# VolcanoHat.net
KiCad netlist of a schematic drawn in EAGLE
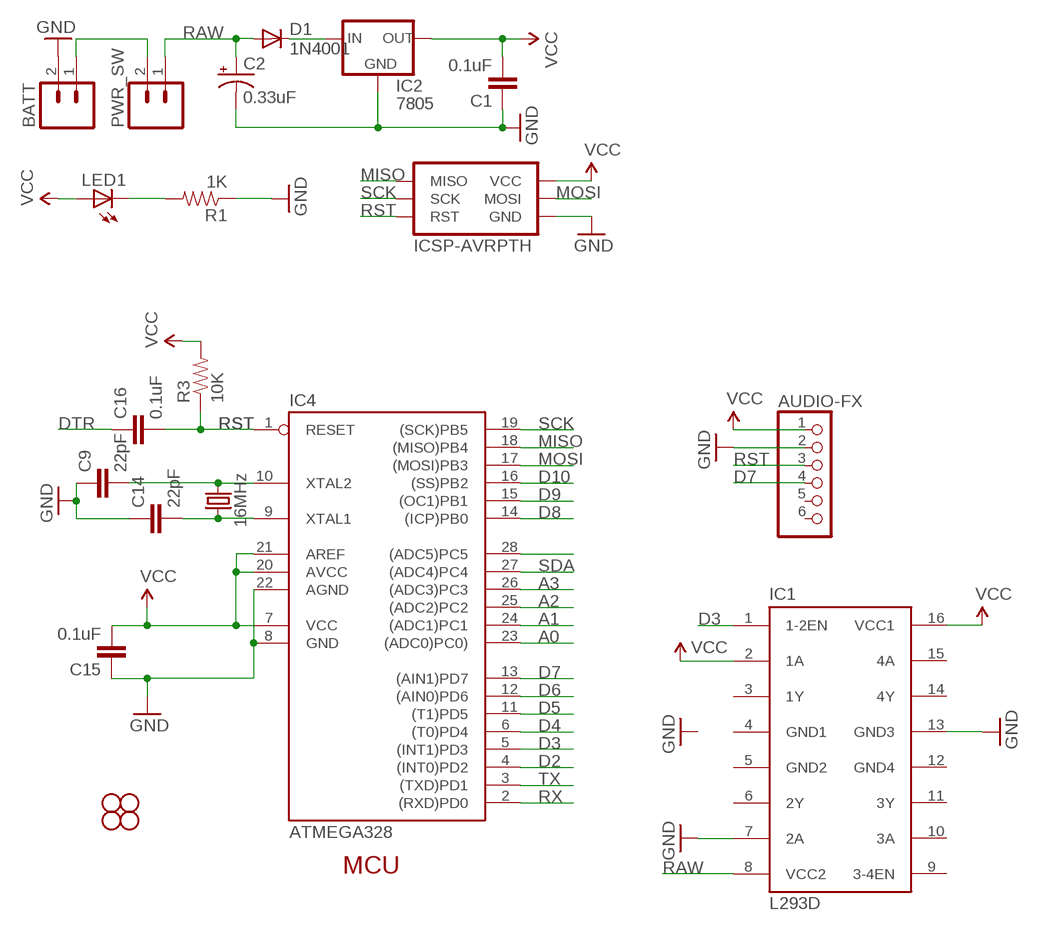
[diagram p0: schematic, sheet 1]

(export (version "E")
  (design (tool "Eeschema 10.0.6"))
  (components
    (comp (ref "AUDIO-FX")
      (value "PINHD-1X6")
      (footprint "eagle-import:1X06")
      (libsource (lib "eagle-import") (part "PINHD-1X6"))
    )
    (comp (ref "BATT")
      (value "M02LOCK_LONGPADS")
      (footprint "eagle-import:1X02_LOCK_LONGPADS")
      (libsource (lib "eagle-import") (part "M02LOCK_LONGPADS"))
    )
    (comp (ref "C1")
      (value "0.1uF")
      (footprint "eagle-import:CAP-PTH-SMALL2")
      (libsource (lib "eagle-import") (part "CAPPTH2"))
    )
    (comp (ref "C2")
      (value "0.33uF")
      (footprint "eagle-import:CPOL-RADIAL-10UF-25V")
      (libsource (lib "eagle-import") (part "CAP_POLPTH2"))
    )
    (comp (ref "C9")
      (value "22pF")
      (footprint "eagle-import:CAP-PTH-SMALL2")
      (libsource (lib "eagle-import") (part "CAPPTH2"))
    )
    (comp (ref "C14")
      (value "22pF")
      (footprint "eagle-import:CAP-PTH-SMALL2")
      (libsource (lib "eagle-import") (part "CAPPTH2"))
    )
    (comp (ref "C15")
      (value "0.1uF")
      (footprint "eagle-import:CAP-PTH-SMALL2")
      (libsource (lib "eagle-import") (part "CAPPTH2"))
    )
    (comp (ref "C16")
      (value "0.1uF")
      (footprint "eagle-import:CAP-PTH-SMALL2")
      (libsource (lib "eagle-import") (part "CAPPTH2"))
    )
    (comp (ref "D1")
      (value "1N4001")
      (footprint "eagle-import:DIODE-1N4001")
      (libsource (lib "eagle-import") (part "DIODEPTH"))
    )
    (comp (ref "IC1")
      (value "L293D")
      (footprint "eagle-import:DIL16")
      (libsource (lib "eagle-import") (part "L293D"))
    )
    (comp (ref "IC2")
      (value "7805")
      (footprint "eagle-import:TO220-IGO")
      (libsource (lib "eagle-import") (part "V_REG_78XXSINK"))
    )
    (comp (ref "IC4")
      (value "ATMEGA328")
      (footprint "eagle-import:DIL28-3")
      (libsource (lib "eagle-import") (part "AT90S4433P"))
    )
    (comp (ref "ICSP")
      (value "ICSP-AVRPTH")
      (footprint "eagle-import:2X3-SHROUDED")
      (libsource (lib "eagle-import") (part "ICSP-AVRPTH"))
    )
    (comp (ref "JP1")
      (value "STAND-OFF#2")
      (footprint "eagle-import:STAND-OFF-#2")
      (libsource (lib "eagle-import") (part "STAND-OFF#2"))
    )
    (comp (ref "JP2")
      (value "STAND-OFF#2")
      (footprint "eagle-import:STAND-OFF-#2")
      (libsource (lib "eagle-import") (part "STAND-OFF#2"))
    )
    (comp (ref "JP5")
      (value "STAND-OFF#2")
      (footprint "eagle-import:STAND-OFF-#2")
      (libsource (lib "eagle-import") (part "STAND-OFF#2"))
    )
    (comp (ref "JP6")
      (value "STAND-OFF#2")
      (footprint "eagle-import:STAND-OFF-#2")
      (libsource (lib "eagle-import") (part "STAND-OFF#2"))
    )
    (comp (ref "LED1")
      (value "LED5MM")
      (footprint "eagle-import:LED5MM")
      (libsource (lib "eagle-import") (part "LED5MM"))
    )
    (comp (ref "PWR_SW")
      (value "M02LOCK_LONGPADS")
      (footprint "eagle-import:1X02_LOCK_LONGPADS")
      (libsource (lib "eagle-import") (part "M02LOCK_LONGPADS"))
    )
    (comp (ref "R1")
      (value "1K")
      (footprint "eagle-import:AXIAL-0.3")
      (libsource (lib "eagle-import") (part "RESISTORAXIAL-0.3"))
    )
    (comp (ref "R3")
      (value "10K")
      (footprint "eagle-import:AXIAL-0.3")
      (libsource (lib "eagle-import") (part "RESISTORAXIAL-0.3"))
    )
    (comp (ref "Y1")
      (value "16MHz")
      (footprint "eagle-import:HC49US")
      (libsource (lib "eagle-import") (part "CRYSTALHC49US"))
    )
  )
  (nets
    (net (code "1") (name "/A0") (class "Default")
      (node (ref "IC4") (pin "23") (pinfunction "(ADC0)PC0)_23") (pintype "bidirectional"))
    )
    (net (code "2") (name "/A1") (class "Default")
      (node (ref "IC4") (pin "24") (pinfunction "(ADC1)PC1_24") (pintype "bidirectional"))
    )
    (net (code "3") (name "/A2") (class "Default")
      (node (ref "IC4") (pin "25") (pinfunction "(ADC2)PC2_25") (pintype "bidirectional"))
    )
    (net (code "4") (name "/A3") (class "Default")
      (node (ref "IC4") (pin "26") (pinfunction "(ADC3)PC3_26") (pintype "bidirectional"))
    )
    (net (code "5") (name "/D2") (class "Default")
      (node (ref "IC4") (pin "4") (pinfunction "(INT0)PD2_4") (pintype "bidirectional"))
    )
    (net (code "6") (name "/D3") (class "Default")
      (node (ref "IC1") (pin "1") (pinfunction "1-2EN_1") (pintype "input"))
      (node (ref "IC4") (pin "5") (pinfunction "(INT1)PD3_5") (pintype "bidirectional"))
    )
    (net (code "7") (name "/D4") (class "Default")
      (node (ref "IC4") (pin "6") (pinfunction "(T0)PD4_6") (pintype "bidirectional"))
    )
    (net (code "8") (name "/D5") (class "Default")
      (node (ref "IC4") (pin "11") (pinfunction "(T1)PD5_11") (pintype "bidirectional"))
    )
    (net (code "9") (name "/D6") (class "Default")
      (node (ref "IC4") (pin "12") (pinfunction "(AIN0)PD6_12") (pintype "bidirectional"))
    )
    (net (code "10") (name "/D7") (class "Default")
      (node (ref "AUDIO-FX") (pin "4") (pinfunction "4_4") (pintype "passive"))
      (node (ref "IC4") (pin "13") (pinfunction "(AIN1)PD7_13") (pintype "bidirectional"))
    )
    (net (code "11") (name "/D8") (class "Default")
      (node (ref "IC4") (pin "14") (pinfunction "(ICP)PB0_14") (pintype "bidirectional"))
    )
    (net (code "12") (name "/D9") (class "Default")
      (node (ref "IC4") (pin "15") (pinfunction "(OC1)PB1_15") (pintype "bidirectional"))
    )
    (net (code "13") (name "/D10") (class "Default")
      (node (ref "IC4") (pin "16") (pinfunction "(SS)PB2_16") (pintype "bidirectional"))
    )
    (net (code "14") (name "/DTR") (class "Default")
      (node (ref "C16") (pin "1") (pinfunction "1_1") (pintype "passive"))
    )
    (net (code "15") (name "/GND1") (class "Default")
      (node (ref "IC1") (pin "4") (pinfunction "GND1_4") (pintype "power_in"))
    )
    (net (code "16") (name "/GND2") (class "Default")
      (node (ref "IC1") (pin "5") (pinfunction "GND2_5") (pintype "power_in"))
    )
    (net (code "17") (name "/GND4") (class "Default")
      (node (ref "IC1") (pin "12") (pinfunction "GND4_12") (pintype "power_in"))
    )
    (net (code "18") (name "/MISO") (class "Default")
      (node (ref "IC4") (pin "18") (pinfunction "(MISO)PB4_18") (pintype "bidirectional"))
      (node (ref "ICSP") (pin "1") (pinfunction "MISO_1") (pintype "bidirectional"))
    )
    (net (code "19") (name "/MOSI") (class "Default")
      (node (ref "IC4") (pin "17") (pinfunction "(MOSI)PB3_17") (pintype "bidirectional"))
      (node (ref "ICSP") (pin "4") (pinfunction "MOSI_4") (pintype "bidirectional"))
    )
    (net (code "20") (name "/RAW") (class "Default")
      (node (ref "C2") (pin "1") (pinfunction "+_1") (pintype "passive"))
      (node (ref "D1") (pin "A") (pinfunction "A_A") (pintype "passive"))
      (node (ref "IC1") (pin "8") (pinfunction "VCC2_8") (pintype "power_in"))
      (node (ref "PWR_SW") (pin "1") (pinfunction "1_1") (pintype "passive"))
    )
    (net (code "21") (name "/RST") (class "Default")
      (node (ref "AUDIO-FX") (pin "3") (pinfunction "3_3") (pintype "passive"))
      (node (ref "C16") (pin "2") (pinfunction "2_2") (pintype "passive"))
      (node (ref "IC4") (pin "1") (pinfunction "RESET_1") (pintype "input"))
      (node (ref "ICSP") (pin "5") (pinfunction "RST_5") (pintype "bidirectional"))
      (node (ref "R3") (pin "P$1") (pinfunction "1_P$1") (pintype "passive"))
    )
    (net (code "22") (name "/RX") (class "Default")
      (node (ref "IC4") (pin "2") (pinfunction "(RXD)PD0_2") (pintype "bidirectional"))
    )
    (net (code "23") (name "/SCK") (class "Default")
      (node (ref "IC4") (pin "19") (pinfunction "(SCK)PB5_19") (pintype "bidirectional"))
      (node (ref "ICSP") (pin "3") (pinfunction "SCK_3") (pintype "bidirectional"))
    )
    (net (code "24") (name "/SDA") (class "Default")
      (node (ref "IC4") (pin "27") (pinfunction "(ADC4)PC4_27") (pintype "bidirectional"))
    )
    (net (code "25") (name "/TX") (class "Default")
      (node (ref "IC4") (pin "3") (pinfunction "(TXD)PD1_3") (pintype "bidirectional"))
    )
    (net (code "26") (name "GND") (class "Default")
      (node (ref "AUDIO-FX") (pin "2") (pinfunction "2_2") (pintype "passive"))
      (node (ref "BATT") (pin "2") (pinfunction "2_2") (pintype "passive"))
      (node (ref "C1") (pin "1") (pinfunction "1_1") (pintype "passive"))
      (node (ref "C14") (pin "1") (pinfunction "1_1") (pintype "passive"))
      (node (ref "C15") (pin "1") (pinfunction "1_1") (pintype "passive"))
      (node (ref "C2") (pin "2") (pinfunction "-_2") (pintype "passive"))
      (node (ref "C9") (pin "1") (pinfunction "1_1") (pintype "passive"))
      (node (ref "IC1") (pin "13") (pinfunction "GND3_13") (pintype "power_in"))
      (node (ref "IC1") (pin "7") (pinfunction "2A_7") (pintype "input"))
      (node (ref "IC2") (pin "GND") (pinfunction "GND_GND") (pintype "input"))
      (node (ref "IC4") (pin "22") (pinfunction "AGND_22") (pintype "power_in"))
      (node (ref "IC4") (pin "8") (pinfunction "GND_8") (pintype "power_in"))
      (node (ref "ICSP") (pin "6") (pinfunction "GND_6") (pintype "bidirectional"))
      (node (ref "R1") (pin "P$1") (pinfunction "1_P$1") (pintype "passive"))
    )
    (net (code "27") (name "Net-(BATT-Pad1)") (class "Default")
      (node (ref "BATT") (pin "1") (pinfunction "1_1") (pintype "passive"))
      (node (ref "PWR_SW") (pin "2") (pinfunction "2_2") (pintype "passive"))
    )
    (net (code "28") (name "Net-(D1-PadC)") (class "Default")
      (node (ref "D1") (pin "C") (pinfunction "C_C") (pintype "passive"))
      (node (ref "IC2") (pin "IN") (pinfunction "IN_IN") (pintype "input"))
    )
    (net (code "29") (name "Net-(IC4-XTAL1)") (class "Default")
      (node (ref "C14") (pin "2") (pinfunction "2_2") (pintype "passive"))
      (node (ref "IC4") (pin "9") (pinfunction "XTAL1_9") (pintype "bidirectional"))
      (node (ref "Y1") (pin "1") (pinfunction "1_1") (pintype "passive"))
    )
    (net (code "30") (name "Net-(IC4-XTAL2)") (class "Default")
      (node (ref "C9") (pin "2") (pinfunction "2_2") (pintype "passive"))
      (node (ref "IC4") (pin "10") (pinfunction "XTAL2_10") (pintype "bidirectional"))
      (node (ref "Y1") (pin "2") (pinfunction "2_2") (pintype "passive"))
    )
    (net (code "31") (name "Net-(LED1-C)") (class "Default")
      (node (ref "LED1") (pin "K") (pinfunction "C_K") (pintype "passive"))
      (node (ref "R1") (pin "P$2") (pinfunction "2_P$2") (pintype "passive"))
    )
    (net (code "32") (name "VCC") (class "Default")
      (node (ref "AUDIO-FX") (pin "1") (pinfunction "1_1") (pintype "passive"))
      (node (ref "C1") (pin "2") (pinfunction "2_2") (pintype "passive"))
      (node (ref "C15") (pin "2") (pinfunction "2_2") (pintype "passive"))
      (node (ref "IC1") (pin "16") (pinfunction "VCC1_16") (pintype "power_in"))
      (node (ref "IC1") (pin "2") (pinfunction "1A_2") (pintype "input"))
      (node (ref "IC2") (pin "OUT") (pinfunction "OUT_OUT") (pintype "output"))
      (node (ref "IC4") (pin "20") (pinfunction "AVCC_20") (pintype "power_in"))
      (node (ref "IC4") (pin "21") (pinfunction "AREF_21") (pintype "passive"))
      (node (ref "IC4") (pin "7") (pinfunction "VCC_7") (pintype "power_in"))
      (node (ref "ICSP") (pin "2") (pinfunction "VCC_2") (pintype "bidirectional"))
      (node (ref "LED1") (pin "A") (pinfunction "A_A") (pintype "passive"))
      (node (ref "R3") (pin "P$2") (pinfunction "2_P$2") (pintype "passive"))
    )
    (net (code "33") (name "unconnected-(AUDIO-FX-Pad5)") (class "Default")
      (node (ref "AUDIO-FX") (pin "5") (pinfunction "5_5") (pintype "passive"))
    )
    (net (code "34") (name "unconnected-(AUDIO-FX-Pad6)") (class "Default")
      (node (ref "AUDIO-FX") (pin "6") (pinfunction "6_6") (pintype "passive"))
    )
    (net (code "35") (name "unconnected-(IC1-1Y-Pad3)") (class "Default")
      (node (ref "IC1") (pin "3") (pinfunction "1Y_3") (pintype "output"))
    )
    (net (code "36") (name "unconnected-(IC1-2Y-Pad6)") (class "Default")
      (node (ref "IC1") (pin "6") (pinfunction "2Y_6") (pintype "output"))
    )
    (net (code "37") (name "unconnected-(IC1-3-4EN-Pad9)") (class "Default")
      (node (ref "IC1") (pin "9") (pinfunction "3-4EN_9") (pintype "input"))
    )
    (net (code "38") (name "unconnected-(IC1-3A-Pad10)") (class "Default")
      (node (ref "IC1") (pin "10") (pinfunction "3A_10") (pintype "input"))
    )
    (net (code "39") (name "unconnected-(IC1-3Y-Pad11)") (class "Default")
      (node (ref "IC1") (pin "11") (pinfunction "3Y_11") (pintype "output"))
    )
    (net (code "40") (name "unconnected-(IC1-4A-Pad15)") (class "Default")
      (node (ref "IC1") (pin "15") (pinfunction "4A_15") (pintype "input"))
    )
    (net (code "41") (name "unconnected-(IC1-4Y-Pad14)") (class "Default")
      (node (ref "IC1") (pin "14") (pinfunction "4Y_14") (pintype "output"))
    )
    (net (code "42") (name "unconnected-(IC4-(ADC5)PC5-Pad28)") (class "Default")
      (node (ref "IC4") (pin "28") (pinfunction "(ADC5)PC5_28") (pintype "bidirectional"))
    )
  )
)
